# dual15v.net
KiCad netlist of a schematic drawn in EAGLE
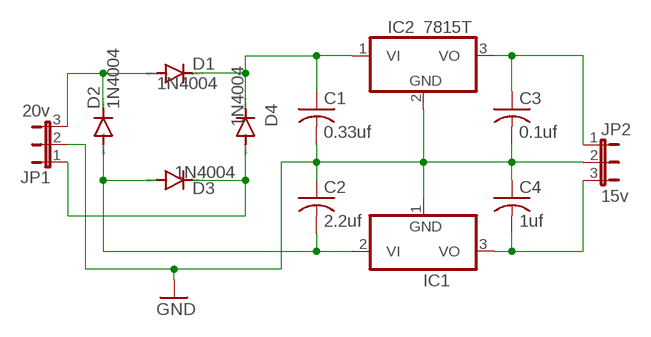
[diagram p0: schematic, sheet 1]

(export (version "E")
  (design (tool "Eeschema 10.0.6"))
  (components
    (comp (ref "C1")
      (value "0.33uf")
      (footprint "eagle-import:C025-025X050")
      (libsource (lib "eagle-import") (part "C-US025-025X050"))
    )
    (comp (ref "C2")
      (value "2.2uf")
      (footprint "eagle-import:C025-025X050")
      (libsource (lib "eagle-import") (part "C-US025-025X050"))
    )
    (comp (ref "C3")
      (value "0.1uf")
      (footprint "eagle-import:C025-025X050")
      (libsource (lib "eagle-import") (part "C-US025-025X050"))
    )
    (comp (ref "C4")
      (value "1uf")
      (footprint "eagle-import:C025-025X050")
      (libsource (lib "eagle-import") (part "C-US025-025X050"))
    )
    (comp (ref "D1")
      (value "1N4004")
      (footprint "eagle-import:DO41-10")
      (libsource (lib "eagle-import") (part "1N4004"))
    )
    (comp (ref "D2")
      (value "1N4004")
      (footprint "eagle-import:DO41-10")
      (libsource (lib "eagle-import") (part "1N4004"))
    )
    (comp (ref "D3")
      (value "1N4004")
      (footprint "eagle-import:DO41-10")
      (libsource (lib "eagle-import") (part "1N4004"))
    )
    (comp (ref "D4")
      (value "1N4004")
      (footprint "eagle-import:DO41-10")
      (libsource (lib "eagle-import") (part "1N4004"))
    )
    (comp (ref "IC1")
      (value "7915T")
      (footprint "eagle-import:TO220H")
      (libsource (lib "eagle-import") (part "79T15"))
    )
    (comp (ref "IC2")
      (value "7815T")
      (footprint "eagle-import:TO220H")
      (libsource (lib "eagle-import") (part "78T15"))
    )
    (comp (ref "JP1")
      (value "20v")
      (footprint "eagle-import:JP2")
      (libsource (lib "eagle-import") (part "JP2E"))
    )
    (comp (ref "JP2")
      (value "15v")
      (footprint "eagle-import:JP2")
      (libsource (lib "eagle-import") (part "JP2E"))
    )
  )
  (nets
    (net (code "1") (name "GND") (class "Default")
      (node (ref "C1") (pin "2") (pinfunction "2_2") (pintype "passive"))
      (node (ref "C2") (pin "1") (pinfunction "1_1") (pintype "passive"))
      (node (ref "C3") (pin "2") (pinfunction "2_2") (pintype "passive"))
      (node (ref "C4") (pin "1") (pinfunction "1_1") (pintype "passive"))
      (node (ref "IC1") (pin "1") (pinfunction "GND_1") (pintype "passive"))
      (node (ref "IC2") (pin "2") (pinfunction "GND_2") (pintype "passive"))
      (node (ref "JP1") (pin "2") (pinfunction "2_2") (pintype "passive"))
      (node (ref "JP2") (pin "2") (pinfunction "2_2") (pintype "passive"))
    )
    (net (code "2") (name "Net-(D1-PadA)") (class "Default")
      (node (ref "D1") (pin "A") (pinfunction "A_A") (pintype "passive"))
      (node (ref "D2") (pin "C") (pinfunction "C_C") (pintype "passive"))
      (node (ref "JP1") (pin "3") (pinfunction "3_3") (pintype "passive"))
    )
    (net (code "3") (name "Net-(D3-PadC)") (class "Default")
      (node (ref "D3") (pin "C") (pinfunction "C_C") (pintype "passive"))
      (node (ref "D4") (pin "A") (pinfunction "A_A") (pintype "passive"))
      (node (ref "JP1") (pin "1") (pinfunction "1_1") (pintype "passive"))
    )
    (net (code "4") (name "Net-(IC1-VI)") (class "Default")
      (node (ref "C2") (pin "2") (pinfunction "2_2") (pintype "passive"))
      (node (ref "D2") (pin "A") (pinfunction "A_A") (pintype "passive"))
      (node (ref "D3") (pin "A") (pinfunction "A_A") (pintype "passive"))
      (node (ref "IC1") (pin "2") (pinfunction "VI_2") (pintype "input"))
    )
    (net (code "5") (name "Net-(IC1-VO)") (class "Default")
      (node (ref "C4") (pin "2") (pinfunction "2_2") (pintype "passive"))
      (node (ref "IC1") (pin "3") (pinfunction "VO_3") (pintype "passive"))
      (node (ref "JP2") (pin "3") (pinfunction "3_3") (pintype "passive"))
    )
    (net (code "6") (name "Net-(IC2-VI)") (class "Default")
      (node (ref "C1") (pin "1") (pinfunction "1_1") (pintype "passive"))
      (node (ref "D1") (pin "C") (pinfunction "C_C") (pintype "passive"))
      (node (ref "D4") (pin "C") (pinfunction "C_C") (pintype "passive"))
      (node (ref "IC2") (pin "1") (pinfunction "VI_1") (pintype "input"))
    )
    (net (code "7") (name "Net-(IC2-VO)") (class "Default")
      (node (ref "C3") (pin "1") (pinfunction "1_1") (pintype "passive"))
      (node (ref "IC2") (pin "3") (pinfunction "VO_3") (pintype "passive"))
      (node (ref "JP2") (pin "1") (pinfunction "1_1") (pintype "passive"))
    )
  )
)
